# MainBoard_V1.net
KiCad netlist of a schematic drawn in EAGLE
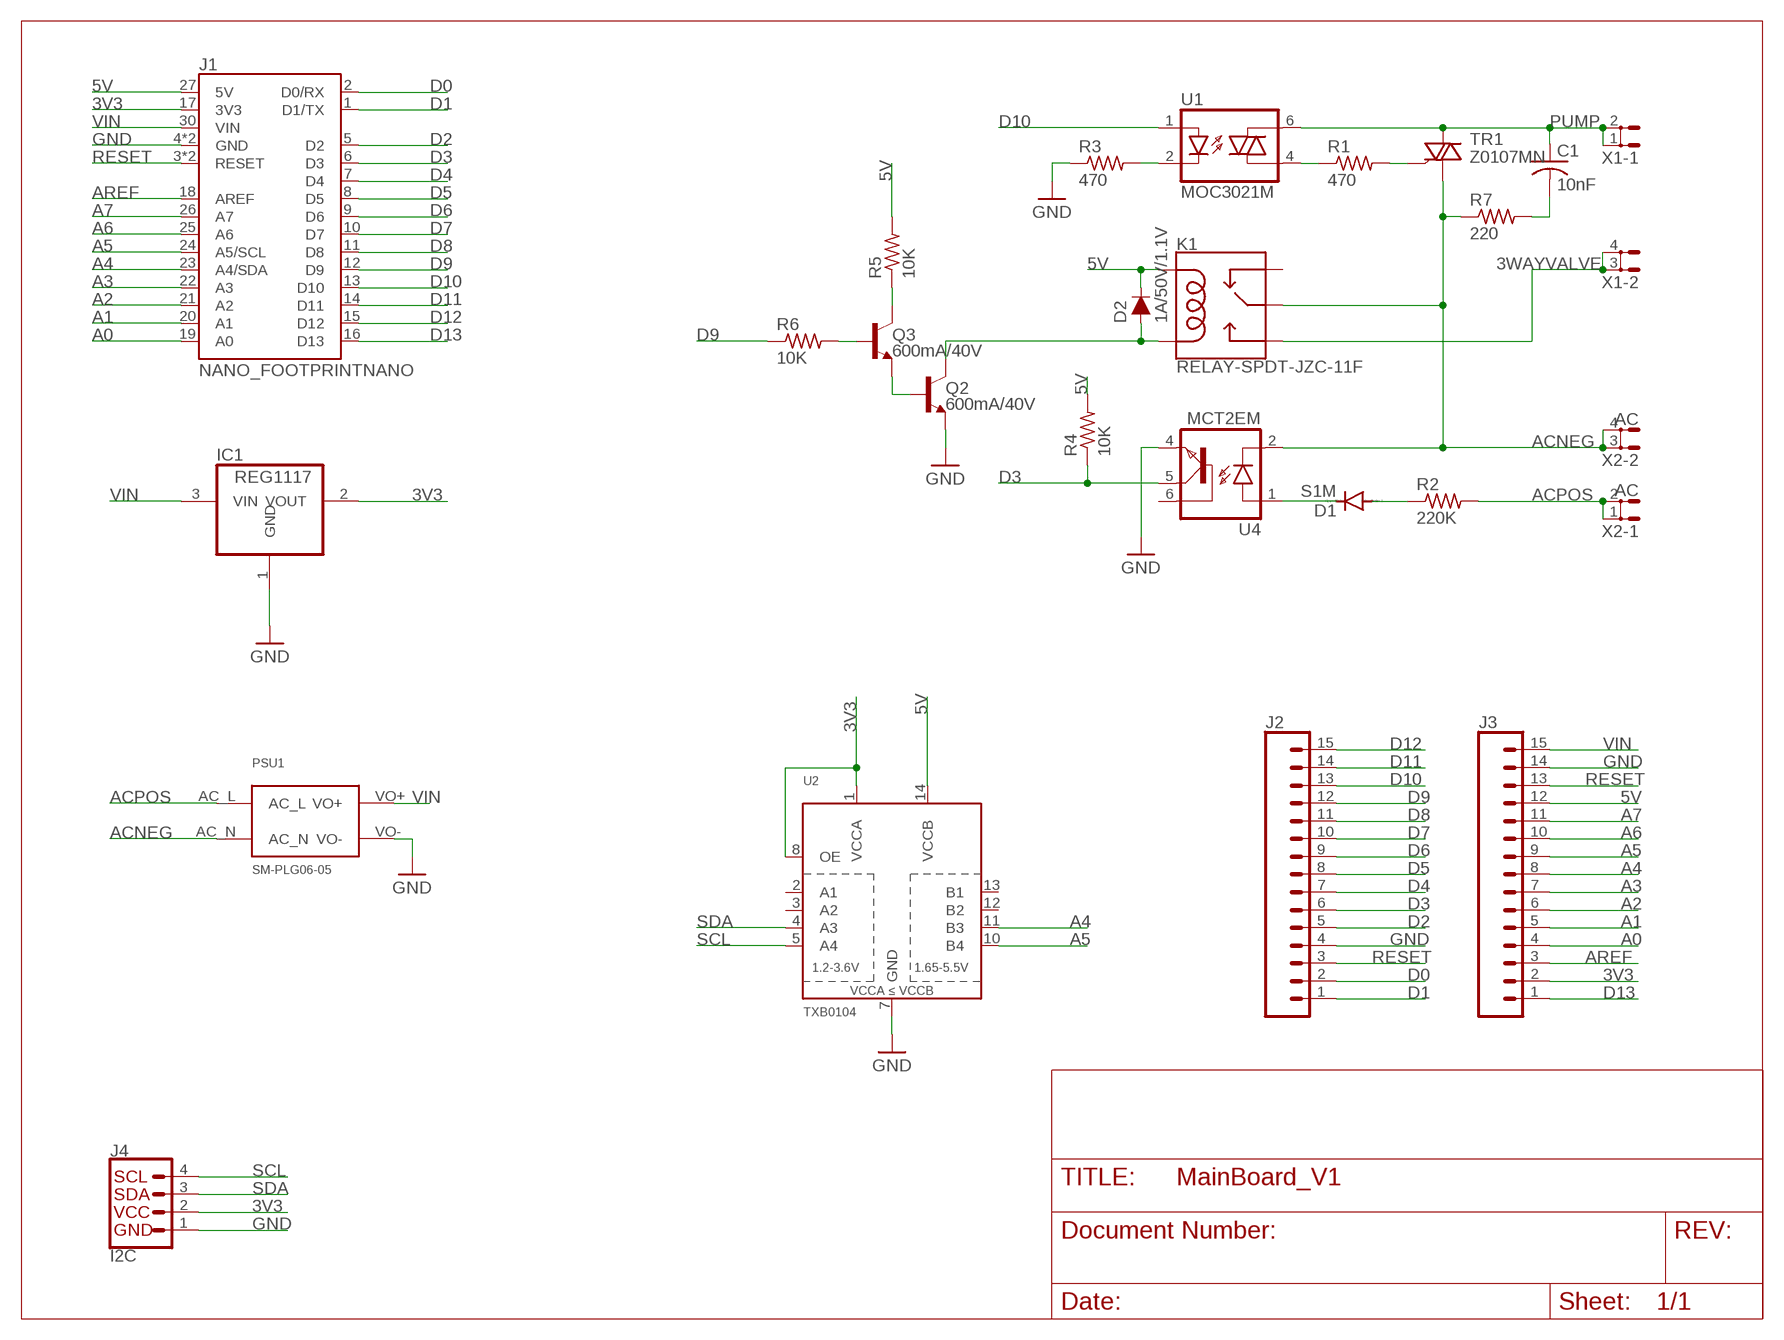
[diagram p0: schematic, sheet 1]

(export (version "E")
  (design (tool "Eeschema 10.0.6"))
  (components
    (comp (ref "C1")
      (value "10nF")
      (footprint "eagle-import:C075-032X103")
      (libsource (lib "eagle-import") (part "C-US075-032X103"))
    )
    (comp (ref "D1")
      (value "S1M")
      (footprint "eagle-import:SMA")
      (libsource (lib "eagle-import") (part "S1M"))
    )
    (comp (ref "D2")
      (value "1A/50V/1.1V")
      (footprint "eagle-import:DIODE-1N4001")
      (libsource (lib "eagle-import") (part "DIODE-PTH"))
    )
    (comp (ref "IC1")
      (value "REG1117")
      (footprint "eagle-import:SOT223")
      (libsource (lib "eagle-import") (part "REG1117"))
    )
    (comp (ref "J1")
      (value "NANO_FOOTPRINTNANO")
      (footprint "eagle-import:NANO")
      (libsource (lib "eagle-import") (part "NANO_FOOTPRINTNANO"))
    )
    (comp (ref "J2")
      (value "CONN_15")
      (footprint "eagle-import:1X15")
      (libsource (lib "eagle-import") (part "CONN_15"))
    )
    (comp (ref "J3")
      (value "CONN_15")
      (footprint "eagle-import:1X15")
      (libsource (lib "eagle-import") (part "CONN_15"))
    )
    (comp (ref "J4")
      (value "I2C")
      (footprint "eagle-import:JST04_1MM_VERT")
      (libsource (lib "eagle-import") (part "QWIIC_CONNECTOR"))
    )
    (comp (ref "K1")
      (value "RELAY-SPDT-JZC-11F")
      (footprint "eagle-import:RELAY-JZC")
      (libsource (lib "eagle-import") (part "RELAY-SPDT-JZC-11F"))
    )
    (comp (ref "PSU1")
      (value "SM-PLG06-05")
      (footprint "eagle-import:SM-PLG06")
      (libsource (lib "eagle-import") (part "SM-PLG06-05"))
    )
    (comp (ref "Q2")
      (value "600mA/40V")
      (footprint "eagle-import:SOT23-3")
      (libsource (lib "eagle-import") (part "TRANS_NPN-MMBT2222AL"))
    )
    (comp (ref "Q3")
      (value "600mA/40V")
      (footprint "eagle-import:SOT23-3")
      (libsource (lib "eagle-import") (part "TRANS_NPN-MMBT2222AL"))
    )
    (comp (ref "R1")
      (value "470")
      (footprint "eagle-import:R0402")
      (libsource (lib "eagle-import") (part "R-US_R0402"))
    )
    (comp (ref "R2")
      (value "220K")
      (footprint "eagle-import:R0603")
      (libsource (lib "eagle-import") (part "R-US_R0603"))
    )
    (comp (ref "R3")
      (value "470")
      (footprint "eagle-import:R0402")
      (libsource (lib "eagle-import") (part "R-US_R0402"))
    )
    (comp (ref "R4")
      (value "10K")
      (footprint "eagle-import:R0402")
      (libsource (lib "eagle-import") (part "R-US_R0402"))
    )
    (comp (ref "R5")
      (value "10K")
      (footprint "eagle-import:R0402")
      (libsource (lib "eagle-import") (part "R-US_R0402"))
    )
    (comp (ref "R6")
      (value "10K")
      (footprint "eagle-import:R0402")
      (libsource (lib "eagle-import") (part "R-US_R0402"))
    )
    (comp (ref "R7")
      (value "220")
      (footprint "eagle-import:R2512")
      (libsource (lib "eagle-import") (part "R-US_R2512"))
    )
    (comp (ref "TR1")
      (value "Z0107MN")
      (footprint "eagle-import:SOT223")
      (libsource (lib "eagle-import") (part "Z0107MNSOT-223"))
    )
    (comp (ref "U1")
      (value "MOC3021M")
      (footprint "eagle-import:DIL06")
      (libsource (lib "eagle-import") (part "MOC3021M"))
    )
    (comp (ref "U2")
      (value "TXB0104")
      (footprint "eagle-import:SO14")
      (libsource (lib "eagle-import") (part "TXB0104PWRSOIC14"))
    )
    (comp (ref "U4")
      (value "MCT2EM")
      (footprint "eagle-import:PDIP6_8P89X6P60_ONS")
      (fields (field (name "COPYRIGHT") "Copyright (C) 2021 Ultra Librarian. All rights reserved."))
      (libsource (lib "eagle-import") (part "MCT2EM"))
    )
    (comp (ref "X1")
      (value "SH5-2")
      (footprint "eagle-import:SH5-2")
      (libsource (lib "eagle-import") (part "SH5-2"))
    )
    (comp (ref "X2")
      (value "AC")
      (footprint "eagle-import:SH5-2")
      (libsource (lib "eagle-import") (part "SH5-2"))
    )
  )
  (nets
    (net (code "1") (name "/3V3") (class "Default")
      (node (ref "IC1") (pin "2") (pinfunction "VOUT_2") (pintype "output"))
      (node (ref "J1") (pin "17") (pinfunction "3V3_17") (pintype "bidirectional"))
      (node (ref "J3") (pin "2") (pinfunction "2_2") (pintype "passive"))
      (node (ref "J4") (pin "2") (pinfunction "2_2") (pintype "power_in"))
      (node (ref "U2") (pin "1") (pinfunction "VCCA_1") (pintype "bidirectional"))
      (node (ref "U2") (pin "8") (pinfunction "OE_8") (pintype "bidirectional"))
    )
    (net (code "2") (name "/3WAYVALVE") (class "Default")
      (node (ref "K1") (pin "3") (pinfunction "NO_3") (pintype "bidirectional"))
      (node (ref "X1") (pin "3") (pinfunction "1_3") (pintype "passive"))
      (node (ref "X1") (pin "4") (pinfunction "2_4") (pintype "passive"))
    )
    (net (code "3") (name "/5V") (class "Default")
      (node (ref "D2") (pin "C") (pinfunction "C_C") (pintype "passive"))
      (node (ref "J1") (pin "27") (pinfunction "5V_27") (pintype "bidirectional"))
      (node (ref "J3") (pin "12") (pinfunction "12_12") (pintype "passive"))
      (node (ref "K1") (pin "5") (pinfunction "COIL1_5") (pintype "bidirectional"))
      (node (ref "R4") (pin "2") (pinfunction "2_2") (pintype "passive"))
      (node (ref "R5") (pin "2") (pinfunction "2_2") (pintype "passive"))
      (node (ref "U2") (pin "14") (pinfunction "VCCB_14") (pintype "bidirectional"))
    )
    (net (code "4") (name "/A0") (class "Default")
      (node (ref "J1") (pin "19") (pinfunction "A0_19") (pintype "bidirectional"))
      (node (ref "J3") (pin "4") (pinfunction "4_4") (pintype "passive"))
    )
    (net (code "5") (name "/A1") (class "Default")
      (node (ref "J1") (pin "20") (pinfunction "A1_20") (pintype "bidirectional"))
      (node (ref "J3") (pin "5") (pinfunction "5_5") (pintype "passive"))
    )
    (net (code "6") (name "/A2") (class "Default")
      (node (ref "J1") (pin "21") (pinfunction "A2_21") (pintype "bidirectional"))
      (node (ref "J3") (pin "6") (pinfunction "6_6") (pintype "passive"))
    )
    (net (code "7") (name "/A3") (class "Default")
      (node (ref "J1") (pin "22") (pinfunction "A3_22") (pintype "bidirectional"))
      (node (ref "J3") (pin "7") (pinfunction "7_7") (pintype "passive"))
    )
    (net (code "8") (name "/A4") (class "Default")
      (node (ref "J1") (pin "23") (pinfunction "A4/SDA_23") (pintype "bidirectional"))
      (node (ref "J3") (pin "8") (pinfunction "8_8") (pintype "passive"))
      (node (ref "U2") (pin "11") (pinfunction "B3_11") (pintype "bidirectional"))
    )
    (net (code "9") (name "/A5") (class "Default")
      (node (ref "J1") (pin "24") (pinfunction "A5/SCL_24") (pintype "bidirectional"))
      (node (ref "J3") (pin "9") (pinfunction "9_9") (pintype "passive"))
      (node (ref "U2") (pin "10") (pinfunction "B4_10") (pintype "bidirectional"))
    )
    (net (code "10") (name "/A6") (class "Default")
      (node (ref "J1") (pin "25") (pinfunction "A6_25") (pintype "bidirectional"))
      (node (ref "J3") (pin "10") (pinfunction "10_10") (pintype "passive"))
    )
    (net (code "11") (name "/A7") (class "Default")
      (node (ref "J1") (pin "26") (pinfunction "A7_26") (pintype "bidirectional"))
      (node (ref "J3") (pin "11") (pinfunction "11_11") (pintype "passive"))
    )
    (net (code "12") (name "/ACNEG") (class "Default")
      (node (ref "K1") (pin "4") (pinfunction "MAIN_4") (pintype "bidirectional"))
      (node (ref "PSU1") (pin "AC_N") (pinfunction "AC_N_AC_N") (pintype "bidirectional"))
      (node (ref "R7") (pin "1") (pinfunction "1_1") (pintype "passive"))
      (node (ref "TR1") (pin "1") (pinfunction "A1_1") (pintype "passive"))
      (node (ref "U4") (pin "2") (pinfunction "C_2") (pintype "passive"))
      (node (ref "X2") (pin "3") (pinfunction "1_3") (pintype "passive"))
      (node (ref "X2") (pin "4") (pinfunction "2_4") (pintype "passive"))
    )
    (net (code "13") (name "/ACPOS") (class "Default")
      (node (ref "PSU1") (pin "AC_L") (pinfunction "AC_L_AC_L") (pintype "bidirectional"))
      (node (ref "R2") (pin "2") (pinfunction "2_2") (pintype "passive"))
      (node (ref "X2") (pin "1") (pinfunction "1_1") (pintype "passive"))
      (node (ref "X2") (pin "2") (pinfunction "2_2") (pintype "passive"))
    )
    (net (code "14") (name "/AREF") (class "Default")
      (node (ref "J1") (pin "18") (pinfunction "AREF_18") (pintype "bidirectional"))
      (node (ref "J3") (pin "3") (pinfunction "3_3") (pintype "passive"))
    )
    (net (code "15") (name "/D0") (class "Default")
      (node (ref "J1") (pin "2") (pinfunction "D0/RX_2") (pintype "bidirectional"))
      (node (ref "J2") (pin "2") (pinfunction "2_2") (pintype "passive"))
    )
    (net (code "16") (name "/D1") (class "Default")
      (node (ref "J1") (pin "1") (pinfunction "D1/TX_1") (pintype "bidirectional"))
      (node (ref "J2") (pin "1") (pinfunction "1_1") (pintype "passive"))
    )
    (net (code "17") (name "/D2") (class "Default")
      (node (ref "J1") (pin "5") (pinfunction "D2_5") (pintype "bidirectional"))
      (node (ref "J2") (pin "5") (pinfunction "5_5") (pintype "passive"))
    )
    (net (code "18") (name "/D3") (class "Default")
      (node (ref "J1") (pin "6") (pinfunction "D3_6") (pintype "bidirectional"))
      (node (ref "J2") (pin "6") (pinfunction "6_6") (pintype "passive"))
      (node (ref "R4") (pin "1") (pinfunction "1_1") (pintype "passive"))
      (node (ref "U4") (pin "5") (pinfunction "COL_5") (pintype "passive"))
    )
    (net (code "19") (name "/D4") (class "Default")
      (node (ref "J1") (pin "7") (pinfunction "D4_7") (pintype "bidirectional"))
      (node (ref "J2") (pin "7") (pinfunction "7_7") (pintype "passive"))
    )
    (net (code "20") (name "/D5") (class "Default")
      (node (ref "J1") (pin "8") (pinfunction "D5_8") (pintype "bidirectional"))
      (node (ref "J2") (pin "8") (pinfunction "8_8") (pintype "passive"))
    )
    (net (code "21") (name "/D6") (class "Default")
      (node (ref "J1") (pin "9") (pinfunction "D6_9") (pintype "bidirectional"))
      (node (ref "J2") (pin "9") (pinfunction "9_9") (pintype "passive"))
    )
    (net (code "22") (name "/D7") (class "Default")
      (node (ref "J1") (pin "10") (pinfunction "D7_10") (pintype "bidirectional"))
      (node (ref "J2") (pin "10") (pinfunction "10_10") (pintype "passive"))
    )
    (net (code "23") (name "/D8") (class "Default")
      (node (ref "J1") (pin "11") (pinfunction "D8_11") (pintype "bidirectional"))
      (node (ref "J2") (pin "11") (pinfunction "11_11") (pintype "passive"))
    )
    (net (code "24") (name "/D9") (class "Default")
      (node (ref "J1") (pin "12") (pinfunction "D9_12") (pintype "bidirectional"))
      (node (ref "J2") (pin "12") (pinfunction "12_12") (pintype "passive"))
      (node (ref "R6") (pin "1") (pinfunction "1_1") (pintype "passive"))
    )
    (net (code "25") (name "/D10") (class "Default")
      (node (ref "J1") (pin "13") (pinfunction "D10_13") (pintype "bidirectional"))
      (node (ref "J2") (pin "13") (pinfunction "13_13") (pintype "passive"))
      (node (ref "U1") (pin "1") (pinfunction "A_1") (pintype "passive"))
    )
    (net (code "26") (name "/D11") (class "Default")
      (node (ref "J1") (pin "14") (pinfunction "D11_14") (pintype "bidirectional"))
      (node (ref "J2") (pin "14") (pinfunction "14_14") (pintype "passive"))
    )
    (net (code "27") (name "/D12") (class "Default")
      (node (ref "J1") (pin "15") (pinfunction "D12_15") (pintype "bidirectional"))
      (node (ref "J2") (pin "15") (pinfunction "15_15") (pintype "passive"))
    )
    (net (code "28") (name "/D13") (class "Default")
      (node (ref "J1") (pin "16") (pinfunction "D13_16") (pintype "bidirectional"))
      (node (ref "J3") (pin "1") (pinfunction "1_1") (pintype "passive"))
    )
    (net (code "29") (name "/PUMP") (class "Default")
      (node (ref "C1") (pin "1") (pinfunction "1_1") (pintype "passive"))
      (node (ref "TR1") (pin "2") (pinfunction "A2_2") (pintype "passive"))
      (node (ref "TR1") (pin "4") (pinfunction "A2_4") (pintype "passive"))
      (node (ref "U1") (pin "6") (pinfunction "A2_6") (pintype "passive"))
      (node (ref "X1") (pin "1") (pinfunction "1_1") (pintype "passive"))
      (node (ref "X1") (pin "2") (pinfunction "2_2") (pintype "passive"))
    )
    (net (code "30") (name "/RESET") (class "Default")
      (node (ref "J1") (pin "28") (pinfunction "RESET_28") (pintype "bidirectional"))
      (node (ref "J1") (pin "3") (pinfunction "RESET_3") (pintype "bidirectional"))
      (node (ref "J2") (pin "3") (pinfunction "3_3") (pintype "passive"))
      (node (ref "J3") (pin "13") (pinfunction "13_13") (pintype "passive"))
    )
    (net (code "31") (name "/SCL") (class "Default")
      (node (ref "J4") (pin "4") (pinfunction "4_4") (pintype "passive"))
      (node (ref "U2") (pin "5") (pinfunction "A4_5") (pintype "bidirectional"))
    )
    (net (code "32") (name "/SDA") (class "Default")
      (node (ref "J4") (pin "3") (pinfunction "3_3") (pintype "passive"))
      (node (ref "U2") (pin "4") (pinfunction "A3_4") (pintype "bidirectional"))
    )
    (net (code "33") (name "/VIN") (class "Default")
      (node (ref "IC1") (pin "3") (pinfunction "VIN_3") (pintype "input"))
      (node (ref "J1") (pin "30") (pinfunction "VIN_30") (pintype "bidirectional"))
      (node (ref "J3") (pin "15") (pinfunction "15_15") (pintype "passive"))
      (node (ref "PSU1") (pin "VO+") (pinfunction "VO+_VO+") (pintype "bidirectional"))
    )
    (net (code "34") (name "GND") (class "Default")
      (node (ref "IC1") (pin "1") (pinfunction "GND_1") (pintype "power_in"))
      (node (ref "J1") (pin "29") (pinfunction "GND_29") (pintype "bidirectional"))
      (node (ref "J1") (pin "4") (pinfunction "GND_4") (pintype "bidirectional"))
      (node (ref "J2") (pin "4") (pinfunction "4_4") (pintype "passive"))
      (node (ref "J3") (pin "14") (pinfunction "14_14") (pintype "passive"))
      (node (ref "J4") (pin "1") (pinfunction "1_1") (pintype "power_in"))
      (node (ref "PSU1") (pin "VO-") (pinfunction "VO-_VO-") (pintype "bidirectional"))
      (node (ref "Q2") (pin "2") (pinfunction "E_2") (pintype "passive"))
      (node (ref "R3") (pin "1") (pinfunction "1_1") (pintype "passive"))
      (node (ref "U2") (pin "7") (pinfunction "GND_7") (pintype "bidirectional"))
      (node (ref "U4") (pin "4") (pinfunction "EMI_4") (pintype "passive"))
    )
    (net (code "35") (name "Net-(C1-Pad2)") (class "Default")
      (node (ref "C1") (pin "2") (pinfunction "2_2") (pintype "passive"))
      (node (ref "R7") (pin "2") (pinfunction "2_2") (pintype "passive"))
    )
    (net (code "36") (name "Net-(D1-PadA)") (class "Default")
      (node (ref "D1") (pin "A") (pinfunction "A_A") (pintype "passive"))
      (node (ref "R2") (pin "1") (pinfunction "1_1") (pintype "passive"))
    )
    (net (code "37") (name "Net-(K1-COIL2)") (class "Default")
      (node (ref "D2") (pin "A") (pinfunction "A_A") (pintype "passive"))
      (node (ref "K1") (pin "1") (pinfunction "COIL2_1") (pintype "bidirectional"))
      (node (ref "Q2") (pin "3") (pinfunction "C_3") (pintype "passive"))
    )
    (net (code "38") (name "Net-(Q2-B)") (class "Default")
      (node (ref "Q2") (pin "1") (pinfunction "B_1") (pintype "passive"))
      (node (ref "Q3") (pin "2") (pinfunction "E_2") (pintype "passive"))
    )
    (net (code "39") (name "Net-(Q3-B)") (class "Default")
      (node (ref "Q3") (pin "1") (pinfunction "B_1") (pintype "passive"))
      (node (ref "R6") (pin "2") (pinfunction "2_2") (pintype "passive"))
    )
    (net (code "40") (name "Net-(Q3-C)") (class "Default")
      (node (ref "Q3") (pin "3") (pinfunction "C_3") (pintype "passive"))
      (node (ref "R5") (pin "1") (pinfunction "1_1") (pintype "passive"))
    )
    (net (code "41") (name "Net-(TR1-G)") (class "Default")
      (node (ref "R1") (pin "2") (pinfunction "2_2") (pintype "passive"))
      (node (ref "TR1") (pin "3") (pinfunction "G_3") (pintype "passive"))
    )
    (net (code "42") (name "Net-(U1-A1)") (class "Default")
      (node (ref "R1") (pin "1") (pinfunction "1_1") (pintype "passive"))
      (node (ref "U1") (pin "4") (pinfunction "A1_4") (pintype "passive"))
    )
    (net (code "43") (name "Net-(U1-C)") (class "Default")
      (node (ref "R3") (pin "2") (pinfunction "2_2") (pintype "passive"))
      (node (ref "U1") (pin "2") (pinfunction "C_2") (pintype "passive"))
    )
    (net (code "44") (name "Net-(U4-A)") (class "Default")
      (node (ref "D1") (pin "C") (pinfunction "C_C") (pintype "passive"))
      (node (ref "U4") (pin "1") (pinfunction "A_1") (pintype "passive"))
    )
    (net (code "45") (name "unconnected-(K1-NC-Pad2)") (class "Default")
      (node (ref "K1") (pin "2") (pinfunction "NC_2") (pintype "bidirectional"))
    )
    (net (code "46") (name "unconnected-(U2-A1-Pad2)") (class "Default")
      (node (ref "U2") (pin "2") (pinfunction "A1_2") (pintype "bidirectional"))
    )
    (net (code "47") (name "unconnected-(U2-A2-Pad3)") (class "Default")
      (node (ref "U2") (pin "3") (pinfunction "A2_3") (pintype "bidirectional"))
    )
    (net (code "48") (name "unconnected-(U2-B1-Pad13)") (class "Default")
      (node (ref "U2") (pin "13") (pinfunction "B1_13") (pintype "bidirectional"))
    )
    (net (code "49") (name "unconnected-(U2-B2-Pad12)") (class "Default")
      (node (ref "U2") (pin "12") (pinfunction "B2_12") (pintype "bidirectional"))
    )
    (net (code "50") (name "unconnected-(U4-BAS-Pad6)") (class "Default")
      (node (ref "U4") (pin "6") (pinfunction "BAS_6") (pintype "passive"))
    )
  )
)
